# holo.net
KiCad netlist of a schematic drawn in EAGLE
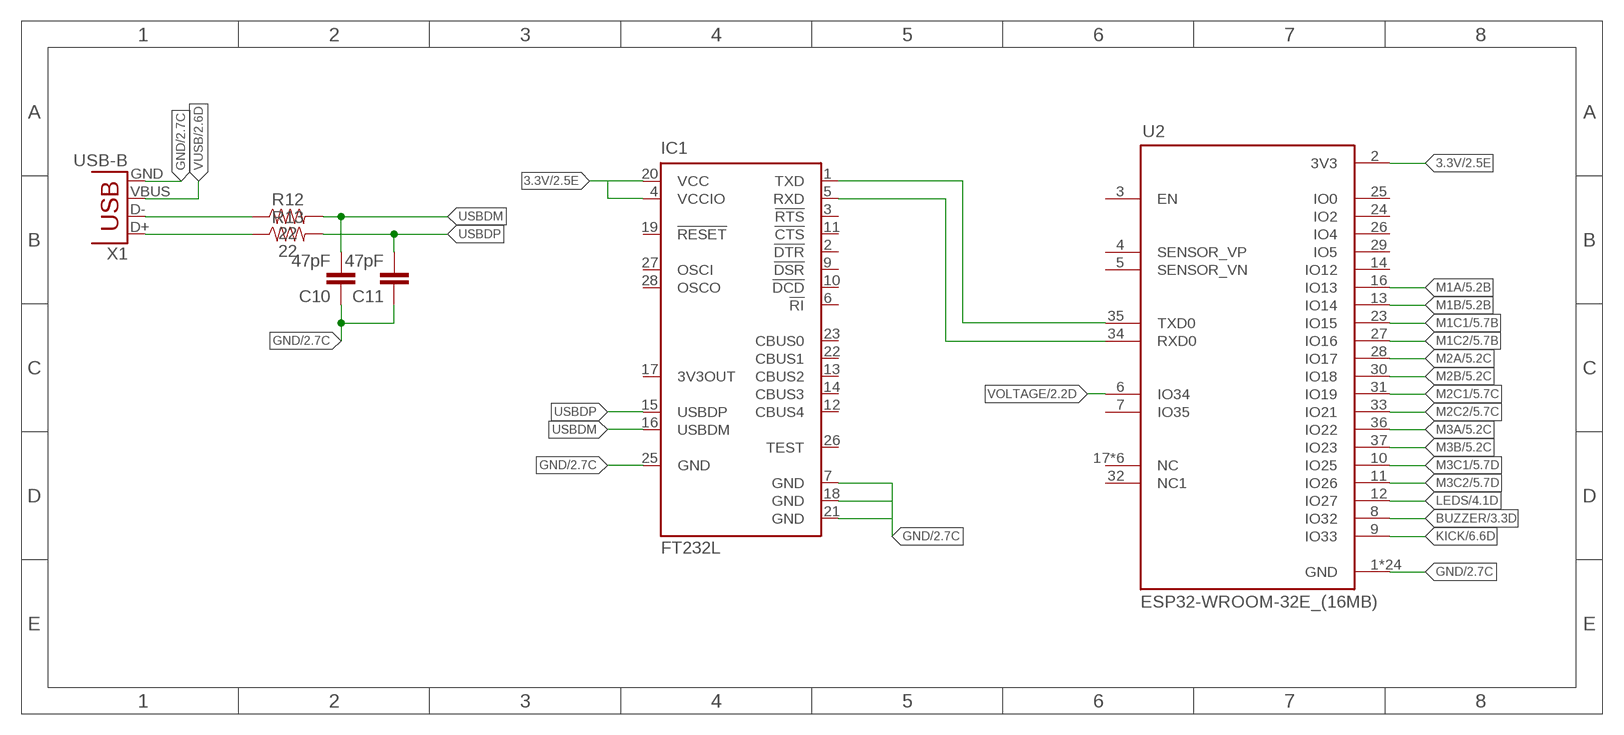
[diagram p0: schematic, sheet 1]
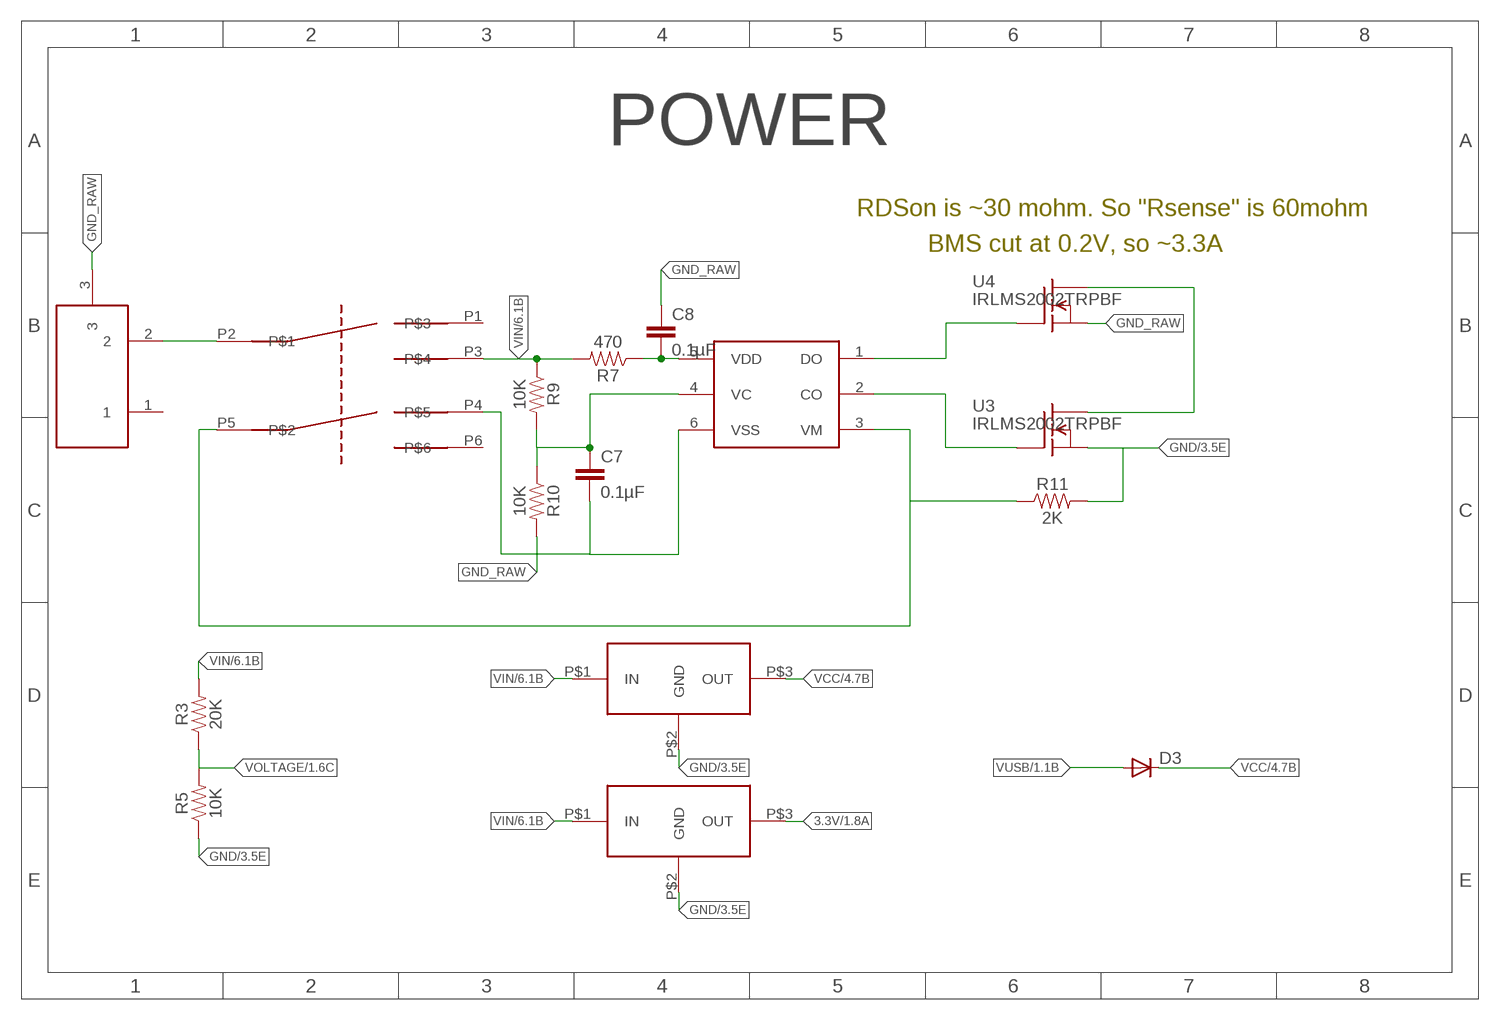
[diagram p1: schematic, sheet 2]
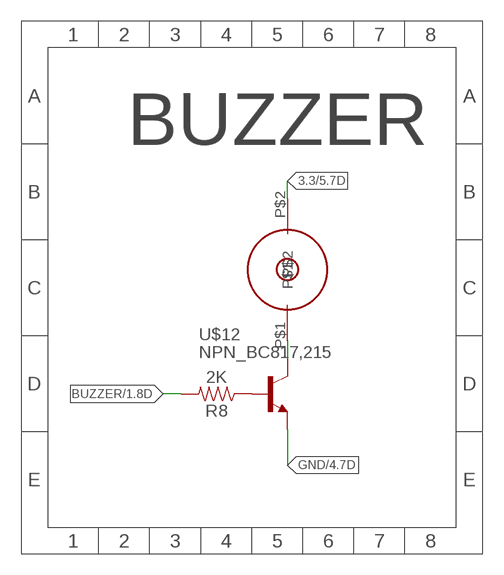
[diagram p2: schematic, sheet 3]
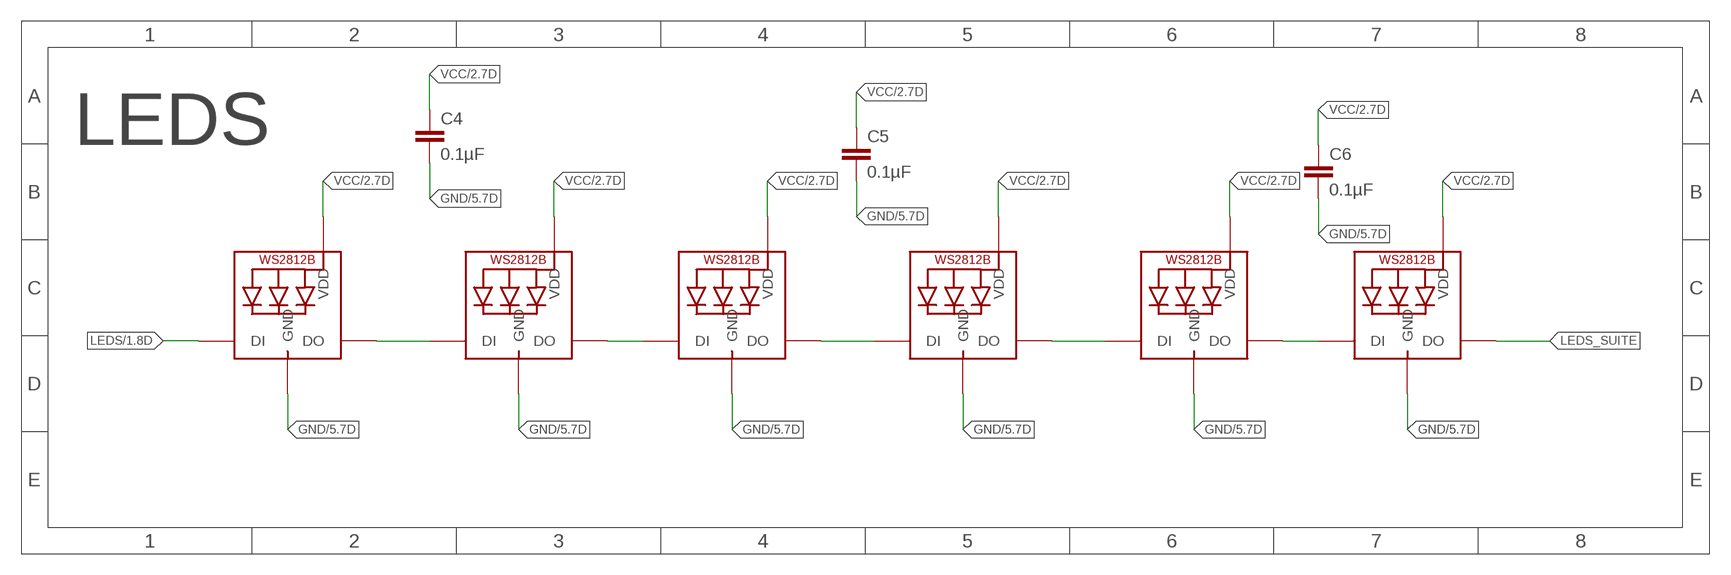
[diagram p3: schematic, sheet 4]
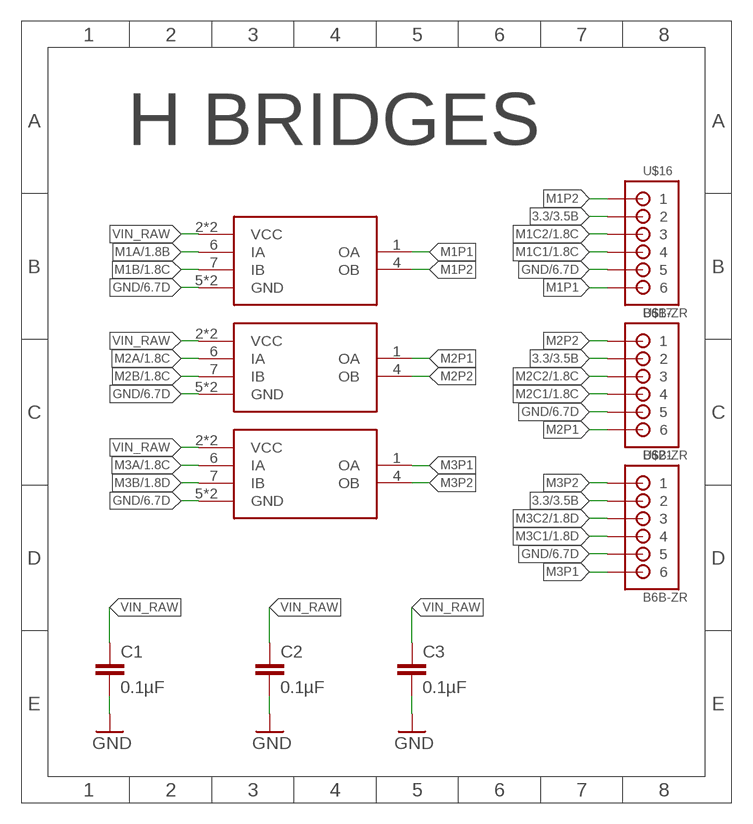
[diagram p4: schematic, sheet 5]
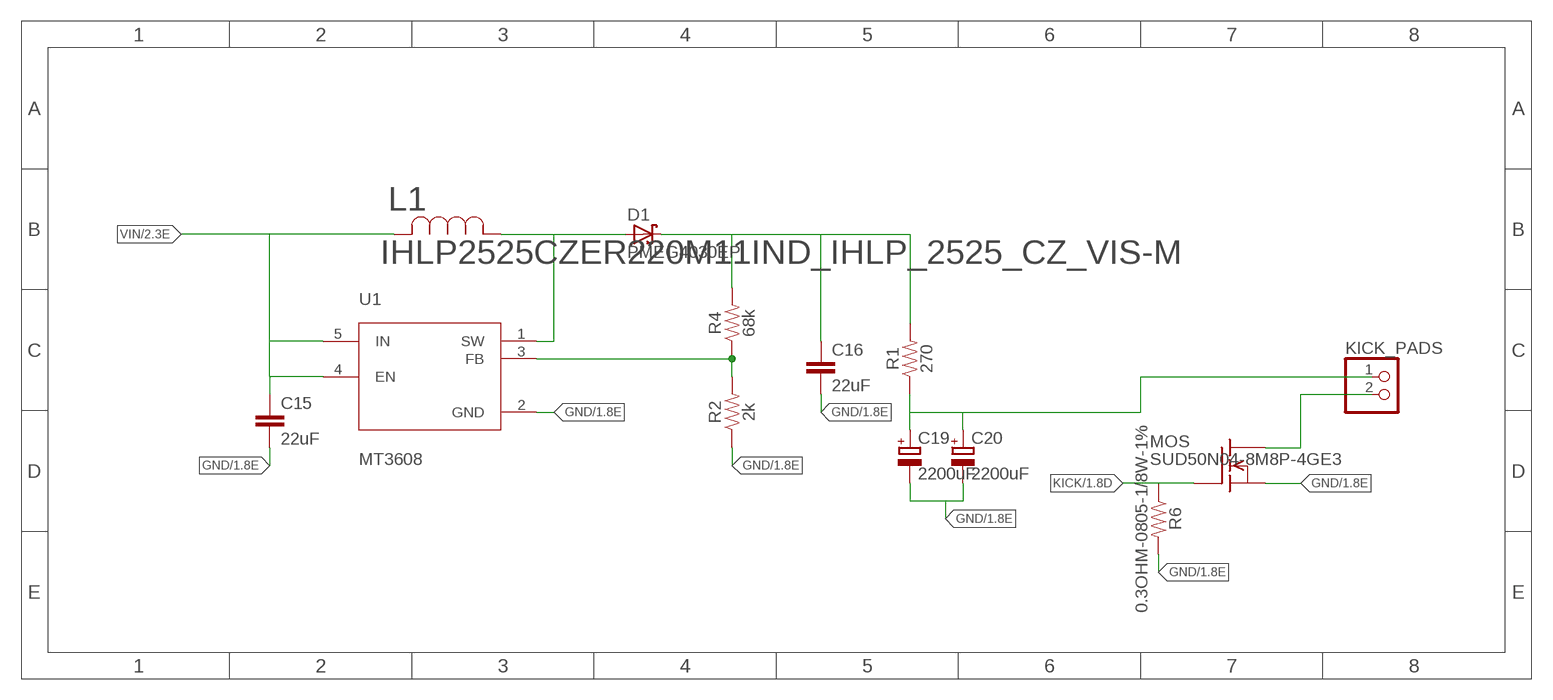
[diagram p5: schematic, sheet 6]

(export (version "E")
  (design (tool "Eeschema 10.0.6"))
  (components
    (comp (ref "C10")
      (value "47pF")
      (footprint "eagle-import:0805")
      (libsource (lib "eagle-import") (part "CAP0805"))
    )
    (comp (ref "C11")
      (value "47pF")
      (footprint "eagle-import:0805")
      (libsource (lib "eagle-import") (part "CAP0805"))
    )
    (comp (ref "IC1")
      (value "FT232L")
      (footprint "eagle-import:SSOP28")
      (fields (field (name "MPN") "FT232RL"))
      (libsource (lib "eagle-import") (part "FT232L"))
    )
    (comp (ref "R12")
      (value "22")
      (footprint "eagle-import:0805")
      (libsource (lib "eagle-import") (part "0.3OHM-0805-1/8W-1%"))
    )
    (comp (ref "R13")
      (value "22")
      (footprint "eagle-import:0805")
      (fields (field (name "PROD_ID") "RES-11622"))
      (libsource (lib "eagle-import") (part "0.3OHM-0805-1/8W-1%"))
    )
    (comp (ref "U2")
      (value "ESP32-WROOM-32E_(16MB)")
      (footprint "eagle-import:MODULE_ESP32-WROOM-32E_(16MB)")
      (fields (field (name "MF") "Espressif Systems") (field (name "MP") "ESP32-WROOM-32E (16MB)"))
      (libsource (lib "eagle-import") (part "ESP32-WROOM-32E_(16MB)"))
    )
    (comp (ref "X1")
      (value "USB-B")
      (footprint "eagle-import:USB-B-PTH")
      (libsource (lib "eagle-import") (part "USBPTH"))
    )
    (comp (ref "C4")
      (value "0.1µF")
      (footprint "eagle-import:0805")
      (libsource (lib "eagle-import") (part "0.33UF/330NF-0805-50V-10%"))
    )
    (comp (ref "C5")
      (value "0.1µF")
      (footprint "eagle-import:0805")
      (fields (field (name "PROD_ID") "CAP-08469"))
      (libsource (lib "eagle-import") (part "0.33UF/330NF-0805-50V-10%"))
    )
    (comp (ref "C6")
      (value "0.1µF")
      (footprint "eagle-import:0805")
      (fields (field (name "PROD_ID") "CAP-08469"))
      (libsource (lib "eagle-import") (part "0.33UF/330NF-0805-50V-10%"))
    )
    (comp (ref "LED1")
      (value "WS2812B5050")
      (footprint "eagle-import:WS2812B")
      (libsource (lib "eagle-import") (part "WS2812B5050"))
    )
    (comp (ref "LED2")
      (value "WS2812B5050")
      (footprint "eagle-import:WS2812B")
      (libsource (lib "eagle-import") (part "WS2812B5050"))
    )
    (comp (ref "LED3")
      (value "WS2812B5050")
      (footprint "eagle-import:WS2812B")
      (libsource (lib "eagle-import") (part "WS2812B5050"))
    )
    (comp (ref "LED4")
      (value "WS2812B5050")
      (footprint "eagle-import:WS2812B")
      (libsource (lib "eagle-import") (part "WS2812B5050"))
    )
    (comp (ref "LED5")
      (value "WS2812B5050")
      (footprint "eagle-import:WS2812B")
      (libsource (lib "eagle-import") (part "WS2812B5050"))
    )
    (comp (ref "LED6")
      (value "WS2812B5050")
      (footprint "eagle-import:WS2812B")
      (libsource (lib "eagle-import") (part "WS2812B5050"))
    )
    (comp (ref "C1")
      (value "0.1µF")
      (footprint "eagle-import:0805")
      (libsource (lib "eagle-import") (part "0.33UF/330NF-0805-50V-10%"))
    )
    (comp (ref "C2")
      (value "0.1µF")
      (footprint "eagle-import:0805")
      (fields (field (name "PROD_ID") "CAP-08469"))
      (libsource (lib "eagle-import") (part "0.33UF/330NF-0805-50V-10%"))
    )
    (comp (ref "C3")
      (value "0.1µF")
      (footprint "eagle-import:0805")
      (fields (field (name "PROD_ID") "CAP-08469"))
      (libsource (lib "eagle-import") (part "0.33UF/330NF-0805-50V-10%"))
    )
    (comp (ref "HB1")
      (value "L9110")
      (footprint "eagle-import:SO8")
      (libsource (lib "eagle-import") (part "L9110"))
    )
    (comp (ref "HB2")
      (value "L9110")
      (footprint "eagle-import:SO8")
      (libsource (lib "eagle-import") (part "L9110"))
    )
    (comp (ref "HB3")
      (value "L9110")
      (footprint "eagle-import:SO8")
      (libsource (lib "eagle-import") (part "L9110"))
    )
    (comp (ref "U$16")
      (value "B6B-ZR")
      (footprint "eagle-import:B6B-ZR")
      (libsource (lib "eagle-import") (part "B6B-ZR"))
    )
    (comp (ref "U$17")
      (value "B6B-ZR")
      (footprint "eagle-import:B6B-ZR")
      (libsource (lib "eagle-import") (part "B6B-ZR"))
    )
    (comp (ref "U$21")
      (value "B6B-ZR")
      (footprint "eagle-import:B6B-ZR")
      (libsource (lib "eagle-import") (part "B6B-ZR"))
    )
    (comp (ref "C7")
      (value "0.1µF")
      (footprint "eagle-import:0805")
      (libsource (lib "eagle-import") (part "0.33UF/330NF-0805-50V-10%"))
    )
    (comp (ref "C8")
      (value "0.1µF")
      (footprint "eagle-import:0805")
      (fields (field (name "PROD_ID") "CAP-08469"))
      (libsource (lib "eagle-import") (part "0.33UF/330NF-0805-50V-10%"))
    )
    (comp (ref "D3")
      (value "DIODESOD")
      (footprint "eagle-import:SOD-323")
      (libsource (lib "eagle-import") (part "DIODESOD"))
    )
    (comp (ref "R3")
      (value "20K")
      (footprint "eagle-import:0805")
      (libsource (lib "eagle-import") (part "0.3OHM-0805-1/8W-1%"))
    )
    (comp (ref "R5")
      (value "10K")
      (footprint "eagle-import:0805")
      (libsource (lib "eagle-import") (part "0.3OHM-0805-1/8W-1%"))
    )
    (comp (ref "R7")
      (value "470")
      (footprint "eagle-import:0805")
      (libsource (lib "eagle-import") (part "0.3OHM-0805-1/8W-1%"))
    )
    (comp (ref "R9")
      (value "10K")
      (footprint "eagle-import:0805")
      (libsource (lib "eagle-import") (part "0.3OHM-0805-1/8W-1%"))
    )
    (comp (ref "R10")
      (value "10K")
      (footprint "eagle-import:0805")
      (libsource (lib "eagle-import") (part "0.3OHM-0805-1/8W-1%"))
    )
    (comp (ref "R11")
      (value "2K")
      (footprint "eagle-import:0805")
      (libsource (lib "eagle-import") (part "0.3OHM-0805-1/8W-1%"))
    )
    (comp (ref "REG")
      (value "REG_5V")
      (footprint "eagle-import:TRACOPOWER")
      (libsource (lib "eagle-import") (part "REG_5V"))
    )
    (comp (ref "REG1")
      (value "REG_5V")
      (footprint "eagle-import:TRACOPOWER")
      (libsource (lib "eagle-import") (part "REG_5V"))
    )
    (comp (ref "U$7")
      (value "S8252")
      (footprint "eagle-import:SOT23-6")
      (libsource (lib "eagle-import") (part "S8252"))
    )
    (comp (ref "U$14")
      (value "DPDT")
      (footprint "eagle-import:L202021MA04Q")
      (libsource (lib "eagle-import") (part "DPDT"))
    )
    (comp (ref "U3")
      (value "IRLMS2002TRPBF")
      (footprint "eagle-import:SOT23-6")
      (libsource (lib "eagle-import") (part "IRLMS2002TRPBF"))
    )
    (comp (ref "U4")
      (value "IRLMS2002TRPBF")
      (footprint "eagle-import:SOT23-6")
      (libsource (lib "eagle-import") (part "IRLMS2002TRPBF"))
    )
    (comp (ref "X2")
      (value "DC21MMX")
      (footprint "eagle-import:DC-21MM")
      (libsource (lib "eagle-import") (part "DC21MMX"))
    )
    (comp (ref "R8")
      (value "2K")
      (footprint "eagle-import:0805")
      (libsource (lib "eagle-import") (part "0.3OHM-0805-1/8W-1%"))
    )
    (comp (ref "U$12")
      (value "NPN_BC817,215")
      (footprint "eagle-import:SOT-23")
      (libsource (lib "eagle-import") (part "NPN_BC817,215"))
    )
    (comp (ref "U$13")
      (value "BUZZER66")
      (footprint "eagle-import:BUZZER66")
      (libsource (lib "eagle-import") (part "BUZZER66"))
    )
    (comp (ref "C15")
      (value "22uF")
      (footprint "eagle-import:C0805")
      (libsource (lib "eagle-import") (part "C-EUC0805"))
    )
    (comp (ref "C16")
      (value "22uF")
      (footprint "eagle-import:C0805")
      (libsource (lib "eagle-import") (part "C-EUC0805"))
    )
    (comp (ref "C19")
      (value "2200uF")
      (footprint "eagle-import:E5-13")
      (libsource (lib "eagle-import") (part "CPOL-EUE5-13"))
    )
    (comp (ref "C20")
      (value "2200uF")
      (footprint "eagle-import:E5-13")
      (libsource (lib "eagle-import") (part "CPOL-EUE5-13"))
    )
    (comp (ref "D1")
      (value "PMEG4030EP")
      (footprint "eagle-import:SOD128")
      (libsource (lib "eagle-import") (part "PMEG4030EP"))
    )
    (comp (ref "KICK_PADS")
      (value "KICKER")
      (footprint "eagle-import:KICKER")
      (libsource (lib "eagle-import") (part "KICKER"))
    )
    (comp (ref "L1")
      (value "IHLP2525CZER220M11IND_IHLP_2525_CZ_VIS-M")
      (footprint "eagle-import:IND_IHLP_2525_CZ_VIS-M")
      (fields (field (name "MANUFACTURER_PART_NUMBER") "IHLP2525CZER220M11"))
      (libsource (lib "eagle-import") (part "IHLP2525CZER220M11IND_IHLP_2525_CZ_VIS-M"))
    )
    (comp (ref "MOS")
      (value "SUD50N04-8M8P-4GE3")
      (footprint "eagle-import:TO252")
      (libsource (lib "eagle-import") (part "SUD50N04-8M8P-4GE3"))
    )
    (comp (ref "R1")
      (value "270")
      (footprint "eagle-import:0805")
      (libsource (lib "eagle-import") (part "0.3OHM-0805-1/8W-1%"))
    )
    (comp (ref "R2")
      (value "2k")
      (footprint "eagle-import:0805")
      (libsource (lib "eagle-import") (part "0.3OHM-0805-1/8W-1%"))
    )
    (comp (ref "R4")
      (value "68k")
      (footprint "eagle-import:0805")
      (libsource (lib "eagle-import") (part "0.3OHM-0805-1/8W-1%"))
    )
    (comp (ref "R6")
      (value "0.3OHM-0805-1/8W-1%")
      (footprint "eagle-import:0805")
      (libsource (lib "eagle-import") (part "0.3OHM-0805-1/8W-1%"))
    )
    (comp (ref "U1")
      (value "MT3608")
      (footprint "eagle-import:SOT95P280X145-6N")
      (fields (field (name "MF") "Aerosemi Technology Co., Ltd"))
      (libsource (lib "eagle-import") (part "MT3608"))
    )
  )
  (nets
    (net (code "1") (name "1") (class "Default")
      (node (ref "X2") (pin "1") (pinfunction "1_1") (pintype "power_in"))
    )
    (net (code "2") (name "3.3") (class "Default")
      (node (ref "U$13") (pin "P$2") (pinfunction "P$2_P$2") (pintype "bidirectional"))
      (node (ref "U$16") (pin "2") (pinfunction "2_2") (pintype "bidirectional"))
      (node (ref "U$17") (pin "2") (pinfunction "2_2") (pintype "bidirectional"))
      (node (ref "U$21") (pin "2") (pinfunction "2_2") (pintype "bidirectional"))
    )
    (net (code "3") (name "3.3V") (class "Default")
      (node (ref "IC1") (pin "20") (pinfunction "VCC_20") (pintype "power_in"))
      (node (ref "IC1") (pin "4") (pinfunction "VCCIO_4") (pintype "power_in"))
      (node (ref "REG1") (pin "P$3") (pinfunction "OUT_P$3") (pintype "bidirectional"))
      (node (ref "U2") (pin "2") (pinfunction "3V3_2") (pintype "power_in"))
    )
    (net (code "4") (name "BUZZER") (class "Default")
      (node (ref "R8") (pin "2") (pinfunction "2_2") (pintype "passive"))
      (node (ref "U2") (pin "8") (pinfunction "IO32_8") (pintype "bidirectional"))
    )
    (net (code "5") (name "GND") (class "Default")
      (node (ref "C1") (pin "2") (pinfunction "2_2") (pintype "passive"))
      (node (ref "C10") (pin "1") (pinfunction "1_1") (pintype "passive"))
      (node (ref "C11") (pin "1") (pinfunction "1_1") (pintype "passive"))
      (node (ref "C15") (pin "2") (pinfunction "2_2") (pintype "passive"))
      (node (ref "C16") (pin "2") (pinfunction "2_2") (pintype "passive"))
      (node (ref "C19") (pin "-") (pinfunction "-_-") (pintype "passive"))
      (node (ref "C2") (pin "2") (pinfunction "2_2") (pintype "passive"))
      (node (ref "C20") (pin "-") (pinfunction "-_-") (pintype "passive"))
      (node (ref "C3") (pin "2") (pinfunction "2_2") (pintype "passive"))
      (node (ref "C4") (pin "2") (pinfunction "2_2") (pintype "passive"))
      (node (ref "C5") (pin "2") (pinfunction "2_2") (pintype "passive"))
      (node (ref "C6") (pin "2") (pinfunction "2_2") (pintype "passive"))
      (node (ref "HB1") (pin "5") (pinfunction "GND_5") (pintype "bidirectional"))
      (node (ref "HB1") (pin "8") (pinfunction "GND_8") (pintype "bidirectional"))
      (node (ref "HB2") (pin "5") (pinfunction "GND_5") (pintype "bidirectional"))
      (node (ref "HB2") (pin "8") (pinfunction "GND_8") (pintype "bidirectional"))
      (node (ref "HB3") (pin "5") (pinfunction "GND_5") (pintype "bidirectional"))
      (node (ref "HB3") (pin "8") (pinfunction "GND_8") (pintype "bidirectional"))
      (node (ref "IC1") (pin "18") (pinfunction "GND_18") (pintype "power_in"))
      (node (ref "IC1") (pin "21") (pinfunction "GND_21") (pintype "power_in"))
      (node (ref "IC1") (pin "25") (pinfunction "GND_25") (pintype "power_in"))
      (node (ref "IC1") (pin "7") (pinfunction "GND_7") (pintype "power_in"))
      (node (ref "LED1") (pin "3-GND") (pinfunction "GND_3-GND") (pintype "power_in"))
      (node (ref "LED2") (pin "3-GND") (pinfunction "GND_3-GND") (pintype "power_in"))
      (node (ref "LED3") (pin "3-GND") (pinfunction "GND_3-GND") (pintype "power_in"))
      (node (ref "LED4") (pin "3-GND") (pinfunction "GND_3-GND") (pintype "power_in"))
      (node (ref "LED5") (pin "3-GND") (pinfunction "GND_3-GND") (pintype "power_in"))
      (node (ref "LED6") (pin "3-GND") (pinfunction "GND_3-GND") (pintype "power_in"))
      (node (ref "MOS") (pin "2") (pinfunction "S_2") (pintype "passive"))
      (node (ref "R11") (pin "2") (pinfunction "2_2") (pintype "passive"))
      (node (ref "R2") (pin "1") (pinfunction "1_1") (pintype "passive"))
      (node (ref "R5") (pin "1") (pinfunction "1_1") (pintype "passive"))
      (node (ref "R6") (pin "2") (pinfunction "2_2") (pintype "passive"))
      (node (ref "REG") (pin "P$2") (pinfunction "GND_P$2") (pintype "bidirectional"))
      (node (ref "REG1") (pin "P$2") (pinfunction "GND_P$2") (pintype "bidirectional"))
      (node (ref "U$12") (pin "2") (pinfunction "E_2") (pintype "passive"))
      (node (ref "U$16") (pin "5") (pinfunction "5_5") (pintype "bidirectional"))
      (node (ref "U$17") (pin "5") (pinfunction "5_5") (pintype "bidirectional"))
      (node (ref "U$21") (pin "5") (pinfunction "5_5") (pintype "bidirectional"))
      (node (ref "U1") (pin "2") (pinfunction "GND_2") (pintype "power_in"))
      (node (ref "U2") (pin "1") (pinfunction "GND_1") (pintype "power_in"))
      (node (ref "U2") (pin "15") (pinfunction "GND_15") (pintype "power_in"))
      (node (ref "U2") (pin "38") (pinfunction "GND_38") (pintype "power_in"))
      (node (ref "U2") (pin "39_1") (pinfunction "GND_39_1") (pintype "power_in"))
      (node (ref "U2") (pin "39_10") (pinfunction "GND_39_10") (pintype "power_in"))
      (node (ref "U2") (pin "39_11") (pinfunction "GND_39_11") (pintype "power_in"))
      (node (ref "U2") (pin "39_12") (pinfunction "GND_39_12") (pintype "power_in"))
      (node (ref "U2") (pin "39_13") (pinfunction "GND_39_13") (pintype "power_in"))
      (node (ref "U2") (pin "39_14") (pinfunction "GND_39_14") (pintype "power_in"))
      (node (ref "U2") (pin "39_15") (pinfunction "GND_39_15") (pintype "power_in"))
      (node (ref "U2") (pin "39_16") (pinfunction "GND_39_16") (pintype "power_in"))
      (node (ref "U2") (pin "39_17") (pinfunction "GND_39_17") (pintype "power_in"))
      (node (ref "U2") (pin "39_18") (pinfunction "GND_39_18") (pintype "power_in"))
      (node (ref "U2") (pin "39_19") (pinfunction "GND_39_19") (pintype "power_in"))
      (node (ref "U2") (pin "39_2") (pinfunction "GND_39_2") (pintype "power_in"))
      (node (ref "U2") (pin "39_20") (pinfunction "GND_39_20") (pintype "power_in"))
      (node (ref "U2") (pin "39_21") (pinfunction "GND_39_21") (pintype "power_in"))
      (node (ref "U2") (pin "39_3") (pinfunction "GND_39_3") (pintype "power_in"))
      (node (ref "U2") (pin "39_4") (pinfunction "GND_39_4") (pintype "power_in"))
      (node (ref "U2") (pin "39_5") (pinfunction "GND_39_5") (pintype "power_in"))
      (node (ref "U2") (pin "39_6") (pinfunction "GND_39_6") (pintype "power_in"))
      (node (ref "U2") (pin "39_7") (pinfunction "GND_39_7") (pintype "power_in"))
      (node (ref "U2") (pin "39_8") (pinfunction "GND_39_8") (pintype "power_in"))
      (node (ref "U2") (pin "39_9") (pinfunction "GND_39_9") (pintype "power_in"))
      (node (ref "U3") (pin "4") (pinfunction "S_4") (pintype "passive"))
      (node (ref "X1") (pin "GND") (pinfunction "GND_GND") (pintype "bidirectional"))
    )
    (net (code "6") (name "GND_RAW") (class "Default")
      (node (ref "C7") (pin "2") (pinfunction "2_2") (pintype "passive"))
      (node (ref "C8") (pin "1") (pinfunction "1_1") (pintype "passive"))
      (node (ref "R10") (pin "2") (pinfunction "2_2") (pintype "passive"))
      (node (ref "U$14") (pin "P4") (pinfunction "P$5_P4") (pintype "bidirectional"))
      (node (ref "U$7") (pin "6") (pinfunction "VSS_6") (pintype "passive"))
      (node (ref "U4") (pin "4") (pinfunction "S_4") (pintype "passive"))
      (node (ref "X2") (pin "3") (pinfunction "3_3") (pintype "power_in"))
    )
    (net (code "7") (name "KICK") (class "Default")
      (node (ref "MOS") (pin "1") (pinfunction "G_1") (pintype "passive"))
      (node (ref "R6") (pin "1") (pinfunction "1_1") (pintype "passive"))
      (node (ref "U2") (pin "9") (pinfunction "IO33_9") (pintype "bidirectional"))
    )
    (net (code "8") (name "LEDS") (class "Default")
      (node (ref "LED1") (pin "4-DIN") (pinfunction "DI_4-DIN") (pintype "input"))
      (node (ref "U2") (pin "12") (pinfunction "IO27_12") (pintype "bidirectional"))
    )
    (net (code "9") (name "LEDS_SUITE") (class "Default")
      (node (ref "LED6") (pin "2-DOUT") (pinfunction "DO_2-DOUT") (pintype "output"))
    )
    (net (code "10") (name "M1A") (class "Default")
      (node (ref "HB1") (pin "6") (pinfunction "IA_6") (pintype "bidirectional"))
      (node (ref "U2") (pin "16") (pinfunction "IO13_16") (pintype "bidirectional"))
    )
    (net (code "11") (name "M1B") (class "Default")
      (node (ref "HB1") (pin "7") (pinfunction "IB_7") (pintype "bidirectional"))
      (node (ref "U2") (pin "13") (pinfunction "IO14_13") (pintype "bidirectional"))
    )
    (net (code "12") (name "M1C1") (class "Default")
      (node (ref "U$16") (pin "4") (pinfunction "4_4") (pintype "bidirectional"))
      (node (ref "U2") (pin "23") (pinfunction "IO15_23") (pintype "bidirectional"))
    )
    (net (code "13") (name "M1C2") (class "Default")
      (node (ref "U$16") (pin "3") (pinfunction "3_3") (pintype "bidirectional"))
      (node (ref "U2") (pin "27") (pinfunction "IO16_27") (pintype "bidirectional"))
    )
    (net (code "14") (name "M1P1") (class "Default")
      (node (ref "HB1") (pin "1") (pinfunction "OA_1") (pintype "bidirectional"))
      (node (ref "U$16") (pin "6") (pinfunction "6_6") (pintype "bidirectional"))
    )
    (net (code "15") (name "M1P2") (class "Default")
      (node (ref "HB1") (pin "4") (pinfunction "OB_4") (pintype "bidirectional"))
      (node (ref "U$16") (pin "1") (pinfunction "1_1") (pintype "bidirectional"))
    )
    (net (code "16") (name "M2A") (class "Default")
      (node (ref "HB2") (pin "6") (pinfunction "IA_6") (pintype "bidirectional"))
      (node (ref "U2") (pin "28") (pinfunction "IO17_28") (pintype "bidirectional"))
    )
    (net (code "17") (name "M2B") (class "Default")
      (node (ref "HB2") (pin "7") (pinfunction "IB_7") (pintype "bidirectional"))
      (node (ref "U2") (pin "30") (pinfunction "IO18_30") (pintype "bidirectional"))
    )
    (net (code "18") (name "M2C1") (class "Default")
      (node (ref "U$17") (pin "4") (pinfunction "4_4") (pintype "bidirectional"))
      (node (ref "U2") (pin "31") (pinfunction "IO19_31") (pintype "bidirectional"))
    )
    (net (code "19") (name "M2C2") (class "Default")
      (node (ref "U$17") (pin "3") (pinfunction "3_3") (pintype "bidirectional"))
      (node (ref "U2") (pin "33") (pinfunction "IO21_33") (pintype "bidirectional"))
    )
    (net (code "20") (name "M2P1") (class "Default")
      (node (ref "HB2") (pin "1") (pinfunction "OA_1") (pintype "bidirectional"))
      (node (ref "U$17") (pin "6") (pinfunction "6_6") (pintype "bidirectional"))
    )
    (net (code "21") (name "M2P2") (class "Default")
      (node (ref "HB2") (pin "4") (pinfunction "OB_4") (pintype "bidirectional"))
      (node (ref "U$17") (pin "1") (pinfunction "1_1") (pintype "bidirectional"))
    )
    (net (code "22") (name "M3A") (class "Default")
      (node (ref "HB3") (pin "6") (pinfunction "IA_6") (pintype "bidirectional"))
      (node (ref "U2") (pin "36") (pinfunction "IO22_36") (pintype "bidirectional"))
    )
    (net (code "23") (name "M3B") (class "Default")
      (node (ref "HB3") (pin "7") (pinfunction "IB_7") (pintype "bidirectional"))
      (node (ref "U2") (pin "37") (pinfunction "IO23_37") (pintype "bidirectional"))
    )
    (net (code "24") (name "M3C1") (class "Default")
      (node (ref "U$21") (pin "4") (pinfunction "4_4") (pintype "bidirectional"))
      (node (ref "U2") (pin "10") (pinfunction "IO25_10") (pintype "bidirectional"))
    )
    (net (code "25") (name "M3C2") (class "Default")
      (node (ref "U$21") (pin "3") (pinfunction "3_3") (pintype "bidirectional"))
      (node (ref "U2") (pin "11") (pinfunction "IO26_11") (pintype "bidirectional"))
    )
    (net (code "26") (name "M3P1") (class "Default")
      (node (ref "HB3") (pin "1") (pinfunction "OA_1") (pintype "bidirectional"))
      (node (ref "U$21") (pin "6") (pinfunction "6_6") (pintype "bidirectional"))
    )
    (net (code "27") (name "M3P2") (class "Default")
      (node (ref "HB3") (pin "4") (pinfunction "OB_4") (pintype "bidirectional"))
      (node (ref "U$21") (pin "1") (pinfunction "1_1") (pintype "bidirectional"))
    )
    (net (code "28") (name "Net-(C19-Pad+)") (class "Default")
      (node (ref "C19") (pin "+") (pinfunction "+_+") (pintype "passive"))
      (node (ref "C20") (pin "+") (pinfunction "+_+") (pintype "passive"))
      (node (ref "KICK_PADS") (pin "1") (pinfunction "1_1") (pintype "passive"))
      (node (ref "R1") (pin "1") (pinfunction "1_1") (pintype "passive"))
    )
    (net (code "29") (name "Net-(D1-A)") (class "Default")
      (node (ref "D1") (pin "2") (pinfunction "A_2") (pintype "passive"))
      (node (ref "L1") (pin "1") (pinfunction "1_1") (pintype "passive"))
      (node (ref "U1") (pin "1") (pinfunction "SW_1") (pintype "output"))
    )
    (net (code "30") (name "Net-(D1-K)") (class "Default")
      (node (ref "C16") (pin "1") (pinfunction "1_1") (pintype "passive"))
      (node (ref "D1") (pin "1") (pinfunction "K_1") (pintype "passive"))
      (node (ref "R1") (pin "2") (pinfunction "2_2") (pintype "passive"))
      (node (ref "R4") (pin "2") (pinfunction "2_2") (pintype "passive"))
    )
    (net (code "31") (name "Net-(IC1-RXD)") (class "Default")
      (node (ref "IC1") (pin "5") (pinfunction "RXD_5") (pintype "input"))
      (node (ref "U2") (pin "34") (pinfunction "RXD0_34") (pintype "bidirectional"))
    )
    (net (code "32") (name "Net-(IC1-TXD)") (class "Default")
      (node (ref "IC1") (pin "1") (pinfunction "TXD_1") (pintype "output"))
      (node (ref "U2") (pin "35") (pinfunction "TXD0_35") (pintype "bidirectional"))
    )
    (net (code "33") (name "Net-(LED1-DO)") (class "Default")
      (node (ref "LED1") (pin "2-DOUT") (pinfunction "DO_2-DOUT") (pintype "output"))
      (node (ref "LED2") (pin "4-DIN") (pinfunction "DI_4-DIN") (pintype "input"))
    )
    (net (code "34") (name "Net-(LED2-DO)") (class "Default")
      (node (ref "LED2") (pin "2-DOUT") (pinfunction "DO_2-DOUT") (pintype "output"))
      (node (ref "LED3") (pin "4-DIN") (pinfunction "DI_4-DIN") (pintype "input"))
    )
    (net (code "35") (name "Net-(LED3-DO)") (class "Default")
      (node (ref "LED3") (pin "2-DOUT") (pinfunction "DO_2-DOUT") (pintype "output"))
      (node (ref "LED4") (pin "4-DIN") (pinfunction "DI_4-DIN") (pintype "input"))
    )
    (net (code "36") (name "Net-(LED4-DO)") (class "Default")
      (node (ref "LED4") (pin "2-DOUT") (pinfunction "DO_2-DOUT") (pintype "output"))
      (node (ref "LED5") (pin "4-DIN") (pinfunction "DI_4-DIN") (pintype "input"))
    )
    (net (code "37") (name "Net-(LED5-DO)") (class "Default")
      (node (ref "LED5") (pin "2-DOUT") (pinfunction "DO_2-DOUT") (pintype "output"))
      (node (ref "LED6") (pin "4-DIN") (pinfunction "DI_4-DIN") (pintype "input"))
    )
    (net (code "38") (name "Net-(MOS-D)") (class "Default")
      (node (ref "KICK_PADS") (pin "2") (pinfunction "2_2") (pintype "passive"))
      (node (ref "MOS") (pin "3") (pinfunction "D_3") (pintype "passive"))
    )
    (net (code "39") (name "Net-(R12-Pad1)") (class "Default")
      (node (ref "R12") (pin "1") (pinfunction "1_1") (pintype "passive"))
      (node (ref "X1") (pin "D-") (pinfunction "D-_D-") (pintype "bidirectional"))
    )
    (net (code "40") (name "Net-(R13-Pad1)") (class "Default")
      (node (ref "R13") (pin "1") (pinfunction "1_1") (pintype "passive"))
      (node (ref "X1") (pin "D+") (pinfunction "D+_D+") (pintype "bidirectional"))
    )
    (net (code "41") (name "Net-(U$7-CO)") (class "Default")
      (node (ref "U$7") (pin "2") (pinfunction "CO_2") (pintype "passive"))
      (node (ref "U3") (pin "3") (pinfunction "G_3") (pintype "passive"))
    )
    (net (code "42") (name "Net-(U$7-DO)") (class "Default")
      (node (ref "U$7") (pin "1") (pinfunction "DO_1") (pintype "passive"))
      (node (ref "U4") (pin "3") (pinfunction "G_3") (pintype "passive"))
    )
    (net (code "43") (name "Net-(U$7-VC)") (class "Default")
      (node (ref "C7") (pin "1") (pinfunction "1_1") (pintype "passive"))
      (node (ref "R10") (pin "1") (pinfunction "1_1") (pintype "passive"))
      (node (ref "R9") (pin "2") (pinfunction "2_2") (pintype "passive"))
      (node (ref "U$7") (pin "4") (pinfunction "VC_4") (pintype "passive"))
    )
    (net (code "44") (name "Net-(U$7-VDD)") (class "Default")
      (node (ref "C8") (pin "2") (pinfunction "2_2") (pintype "passive"))
      (node (ref "R7") (pin "1") (pinfunction "1_1") (pintype "passive"))
      (node (ref "U$7") (pin "5") (pinfunction "VDD_5") (pintype "passive"))
    )
    (net (code "45") (name "Net-(U$12-B)") (class "Default")
      (node (ref "R8") (pin "1") (pinfunction "1_1") (pintype "passive"))
      (node (ref "U$12") (pin "1") (pinfunction "B_1") (pintype "passive"))
    )
    (net (code "46") (name "Net-(U$12-C)") (class "Default")
      (node (ref "U$12") (pin "3") (pinfunction "C_3") (pintype "passive"))
      (node (ref "U$13") (pin "P$1") (pinfunction "P$1_P$1") (pintype "bidirectional"))
    )
    (net (code "47") (name "Net-(U$14-P$1)") (class "Default")
      (node (ref "U$14") (pin "P2") (pinfunction "P$1_P2") (pintype "bidirectional"))
      (node (ref "X2") (pin "2") (pinfunction "2_2") (pintype "power_in"))
    )
    (net (code "48") (name "Net-(U$14-P$2)") (class "Default")
      (node (ref "R11") (pin "1") (pinfunction "1_1") (pintype "passive"))
      (node (ref "U$14") (pin "P5") (pinfunction "P$2_P5") (pintype "bidirectional"))
      (node (ref "U$7") (pin "3") (pinfunction "VM_3") (pintype "passive"))
    )
    (net (code "49") (name "Net-(U1-FB)") (class "Default")
      (node (ref "R2") (pin "2") (pinfunction "2_2") (pintype "passive"))
      (node (ref "R4") (pin "1") (pinfunction "1_1") (pintype "passive"))
      (node (ref "U1") (pin "3") (pinfunction "FB_3") (pintype "input"))
    )
    (net (code "50") (name "Net-(U3-D-Pad1)") (class "Default")
      (node (ref "U3") (pin "1") (pinfunction "D_1") (pintype "passive"))
      (node (ref "U3") (pin "2") (pinfunction "D_2") (pintype "passive"))
      (node (ref "U3") (pin "5") (pinfunction "D_5") (pintype "passive"))
      (node (ref "U3") (pin "6") (pinfunction "D_6") (pintype "passive"))
      (node (ref "U4") (pin "1") (pinfunction "D_1") (pintype "passive"))
      (node (ref "U4") (pin "2") (pinfunction "D_2") (pintype "passive"))
      (node (ref "U4") (pin "5") (pinfunction "D_5") (pintype "passive"))
      (node (ref "U4") (pin "6") (pinfunction "D_6") (pintype "passive"))
    )
    (net (code "51") (name "USBDM") (class "Default")
      (node (ref "C10") (pin "2") (pinfunction "2_2") (pintype "passive"))
      (node (ref "IC1") (pin "16") (pinfunction "USBDM_16") (pintype "bidirectional"))
      (node (ref "R12") (pin "2") (pinfunction "2_2") (pintype "passive"))
    )
    (net (code "52") (name "USBDP") (class "Default")
      (node (ref "C11") (pin "2") (pinfunction "2_2") (pintype "passive"))
      (node (ref "IC1") (pin "15") (pinfunction "USBDP_15") (pintype "bidirectional"))
      (node (ref "R13") (pin "2") (pinfunction "2_2") (pintype "passive"))
    )
    (net (code "53") (name "VCC") (class "Default")
      (node (ref "C4") (pin "1") (pinfunction "1_1") (pintype "passive"))
      (node (ref "C5") (pin "1") (pinfunction "1_1") (pintype "passive"))
      (node (ref "C6") (pin "1") (pinfunction "1_1") (pintype "passive"))
      (node (ref "D3") (pin "1") (pinfunction "C_1") (pintype "passive"))
      (node (ref "LED1") (pin "1-VDD") (pinfunction "VDD_1-VDD") (pintype "power_in"))
      (node (ref "LED2") (pin "1-VDD") (pinfunction "VDD_1-VDD") (pintype "power_in"))
      (node (ref "LED3") (pin "1-VDD") (pinfunction "VDD_1-VDD") (pintype "power_in"))
      (node (ref "LED4") (pin "1-VDD") (pinfunction "VDD_1-VDD") (pintype "power_in"))
      (node (ref "LED5") (pin "1-VDD") (pinfunction "VDD_1-VDD") (pintype "power_in"))
      (node (ref "LED6") (pin "1-VDD") (pinfunction "VDD_1-VDD") (pintype "power_in"))
      (node (ref "REG") (pin "P$3") (pinfunction "OUT_P$3") (pintype "bidirectional"))
    )
    (net (code "54") (name "VIN") (class "Default")
      (node (ref "C15") (pin "1") (pinfunction "1_1") (pintype "passive"))
      (node (ref "L1") (pin "2") (pinfunction "2_2") (pintype "passive"))
      (node (ref "R3") (pin "2") (pinfunction "2_2") (pintype "passive"))
      (node (ref "R7") (pin "2") (pinfunction "2_2") (pintype "passive"))
      (node (ref "R9") (pin "1") (pinfunction "1_1") (pintype "passive"))
      (node (ref "REG") (pin "P$1") (pinfunction "IN_P$1") (pintype "bidirectional"))
      (node (ref "REG1") (pin "P$1") (pinfunction "IN_P$1") (pintype "bidirectional"))
      (node (ref "U$14") (pin "P3") (pinfunction "P$4_P3") (pintype "bidirectional"))
      (node (ref "U1") (pin "4") (pinfunction "EN_4") (pintype "input"))
      (node (ref "U1") (pin "5") (pinfunction "IN_5") (pintype "input"))
    )
    (net (code "55") (name "VIN_RAW") (class "Default")
      (node (ref "C1") (pin "1") (pinfunction "1_1") (pintype "passive"))
      (node (ref "C2") (pin "1") (pinfunction "1_1") (pintype "passive"))
      (node (ref "C3") (pin "1") (pinfunction "1_1") (pintype "passive"))
      (node (ref "HB1") (pin "2") (pinfunction "VCC_2") (pintype "bidirectional"))
      (node (ref "HB1") (pin "3") (pinfunction "VCC_3") (pintype "bidirectional"))
      (node (ref "HB2") (pin "2") (pinfunction "VCC_2") (pintype "bidirectional"))
      (node (ref "HB2") (pin "3") (pinfunction "VCC_3") (pintype "bidirectional"))
      (node (ref "HB3") (pin "2") (pinfunction "VCC_2") (pintype "bidirectional"))
      (node (ref "HB3") (pin "3") (pinfunction "VCC_3") (pintype "bidirectional"))
    )
    (net (code "56") (name "VOLTAGE") (class "Default")
      (node (ref "R3") (pin "1") (pinfunction "1_1") (pintype "passive"))
      (node (ref "R5") (pin "2") (pinfunction "2_2") (pintype "passive"))
      (node (ref "U2") (pin "6") (pinfunction "IO34_6") (pintype "input"))
    )
    (net (code "57") (name "VUSB") (class "Default")
      (node (ref "D3") (pin "2") (pinfunction "A_2") (pintype "passive"))
      (node (ref "X1") (pin "VBUS") (pinfunction "VBUS_VBUS") (pintype "bidirectional"))
    )
    (net (code "58") (name "unconnected-(IC1-3V3OUT-Pad17)") (class "Default")
      (node (ref "IC1") (pin "17") (pinfunction "3V3OUT_17") (pintype "output"))
    )
    (net (code "59") (name "unconnected-(IC1-CBUS0-Pad23)") (class "Default")
      (node (ref "IC1") (pin "23") (pinfunction "CBUS0_23") (pintype "bidirectional"))
    )
    (net (code "60") (name "unconnected-(IC1-CBUS1-Pad22)") (class "Default")
      (node (ref "IC1") (pin "22") (pinfunction "CBUS1_22") (pintype "bidirectional"))
    )
    (net (code "61") (name "unconnected-(IC1-CBUS2-Pad13)") (class "Default")
      (node (ref "IC1") (pin "13") (pinfunction "CBUS2_13") (pintype "bidirectional"))
    )
    (net (code "62") (name "unconnected-(IC1-CBUS3-Pad14)") (class "Default")
      (node (ref "IC1") (pin "14") (pinfunction "CBUS3_14") (pintype "bidirectional"))
    )
    (net (code "63") (name "unconnected-(IC1-CBUS4-Pad12)") (class "Default")
      (node (ref "IC1") (pin "12") (pinfunction "CBUS4_12") (pintype "bidirectional"))
    )
    (net (code "64") (name "unconnected-(IC1-OSCI-Pad27)") (class "Default")
      (node (ref "IC1") (pin "27") (pinfunction "OSCI_27") (pintype "input"))
    )
    (net (code "65") (name "unconnected-(IC1-OSCO-Pad28)") (class "Default")
      (node (ref "IC1") (pin "28") (pinfunction "OSCO_28") (pintype "output"))
    )
    (net (code "66") (name "unconnected-(IC1-TEST-Pad26)") (class "Default")
      (node (ref "IC1") (pin "26") (pinfunction "TEST_26") (pintype "input"))
    )
    (net (code "67") (name "unconnected-(IC1-~{CTS}-Pad11)") (class "Default")
      (node (ref "IC1") (pin "11") (pinfunction "~{CTS}_11") (pintype "input"))
    )
    (net (code "68") (name "unconnected-(IC1-~{DCD}-Pad10)") (class "Default")
      (node (ref "IC1") (pin "10") (pinfunction "~{DCD}_10") (pintype "input"))
    )
    (net (code "69") (name "unconnected-(IC1-~{DSR}-Pad9)") (class "Default")
      (node (ref "IC1") (pin "9") (pinfunction "~{DSR}_9") (pintype "input"))
    )
    (net (code "70") (name "unconnected-(IC1-~{DTR}-Pad2)") (class "Default")
      (node (ref "IC1") (pin "2") (pinfunction "~{DTR}_2") (pintype "output"))
    )
    (net (code "71") (name "unconnected-(IC1-~{RESET}-Pad19)") (class "Default")
      (node (ref "IC1") (pin "19") (pinfunction "~{RESET}_19") (pintype "input"))
    )
    (net (code "72") (name "unconnected-(IC1-~{RI}-Pad6)") (class "Default")
      (node (ref "IC1") (pin "6") (pinfunction "~{RI}_6") (pintype "input"))
    )
    (net (code "73") (name "unconnected-(IC1-~{RTS}-Pad3)") (class "Default")
      (node (ref "IC1") (pin "3") (pinfunction "~{RTS}_3") (pintype "output"))
    )
    (net (code "74") (name "unconnected-(U$14-P$3-PadP1)") (class "Default")
      (node (ref "U$14") (pin "P1") (pinfunction "P$3_P1") (pintype "bidirectional"))
    )
    (net (code "75") (name "unconnected-(U$14-P$6-PadP6)") (class "Default")
      (node (ref "U$14") (pin "P6") (pinfunction "P$6_P6") (pintype "bidirectional"))
    )
    (net (code "76") (name "unconnected-(U2-EN-Pad3)") (class "Default")
      (node (ref "U2") (pin "3") (pinfunction "EN_3") (pintype "input"))
    )
    (net (code "77") (name "unconnected-(U2-IO0-Pad25)") (class "Default")
      (node (ref "U2") (pin "25") (pinfunction "IO0_25") (pintype "bidirectional"))
    )
    (net (code "78") (name "unconnected-(U2-IO2-Pad24)") (class "Default")
      (node (ref "U2") (pin "24") (pinfunction "IO2_24") (pintype "bidirectional"))
    )
    (net (code "79") (name "unconnected-(U2-IO4-Pad26)") (class "Default")
      (node (ref "U2") (pin "26") (pinfunction "IO4_26") (pintype "bidirectional"))
    )
    (net (code "80") (name "unconnected-(U2-IO5-Pad29)") (class "Default")
      (node (ref "U2") (pin "29") (pinfunction "IO5_29") (pintype "bidirectional"))
    )
    (net (code "81") (name "unconnected-(U2-IO12-Pad14)") (class "Default")
      (node (ref "U2") (pin "14") (pinfunction "IO12_14") (pintype "bidirectional"))
    )
    (net (code "82") (name "unconnected-(U2-IO35-Pad7)") (class "Default")
      (node (ref "U2") (pin "7") (pinfunction "IO35_7") (pintype "input"))
    )
    (net (code "83") (name "unconnected-(U2-NC-Pad17)") (class "Default")
      (node (ref "U2") (pin "17") (pinfunction "NC_17") (pintype "no_connect"))
    )
    (net (code "84") (name "unconnected-(U2-NC-Pad18)") (class "Default")
      (node (ref "U2") (pin "18") (pinfunction "NC_18") (pintype "no_connect"))
    )
    (net (code "85") (name "unconnected-(U2-NC-Pad19)") (class "Default")
      (node (ref "U2") (pin "19") (pinfunction "NC_19") (pintype "no_connect"))
    )
    (net (code "86") (name "unconnected-(U2-NC-Pad20)") (class "Default")
      (node (ref "U2") (pin "20") (pinfunction "NC_20") (pintype "no_connect"))
    )
    (net (code "87") (name "unconnected-(U2-NC-Pad21)") (class "Default")
      (node (ref "U2") (pin "21") (pinfunction "NC_21") (pintype "no_connect"))
    )
    (net (code "88") (name "unconnected-(U2-NC-Pad22)") (class "Default")
      (node (ref "U2") (pin "22") (pinfunction "NC_22") (pintype "no_connect"))
    )
    (net (code "89") (name "unconnected-(U2-NC1-Pad32)") (class "Default")
      (node (ref "U2") (pin "32") (pinfunction "NC1_32") (pintype "no_connect"))
    )
    (net (code "90") (name "unconnected-(U2-SENSOR_VN-Pad5)") (class "Default")
      (node (ref "U2") (pin "5") (pinfunction "SENSOR_VN_5") (pintype "input"))
    )
    (net (code "91") (name "unconnected-(U2-SENSOR_VP-Pad4)") (class "Default")
      (node (ref "U2") (pin "4") (pinfunction "SENSOR_VP_4") (pintype "input"))
    )
  )
)
